# WiLo_V1_0.net
KiCad netlist of a schematic drawn in EAGLE
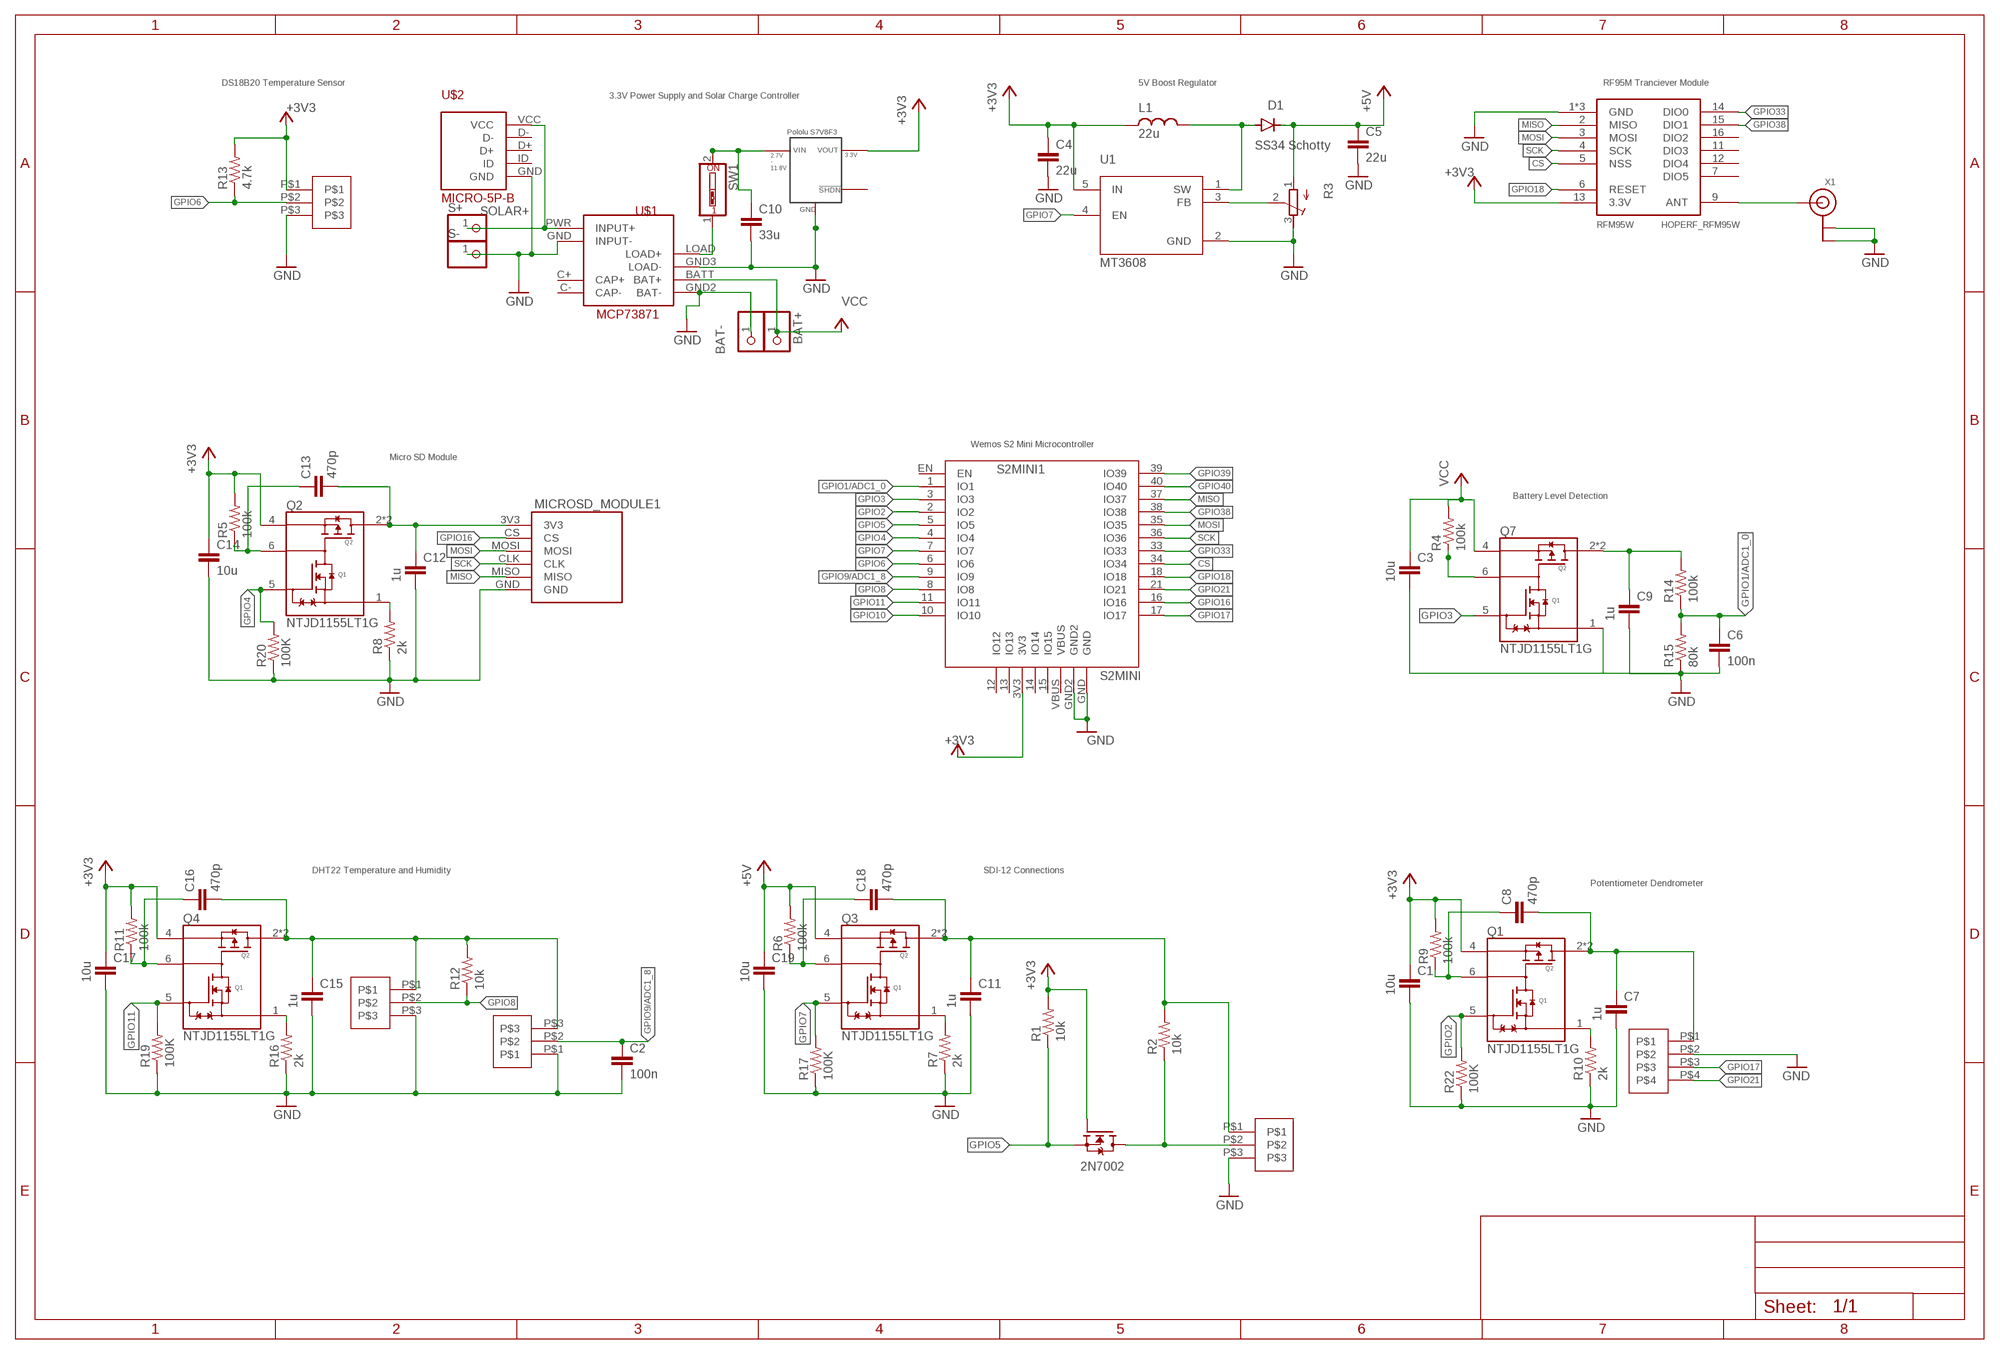
[diagram p0: schematic, sheet 1]

(export (version "E")
  (design (tool "Eeschema 10.0.6"))
  (components
    (comp (ref "BAT+")
      (value "PINHD-1X1")
      (footprint "eagle-import:1X01")
      (libsource (lib "eagle-import") (part "PINHD-1X1"))
    )
    (comp (ref "BAT-")
      (value "PINHD-1X1")
      (footprint "eagle-import:1X01")
      (libsource (lib "eagle-import") (part "PINHD-1X1"))
    )
    (comp (ref "C1")
      (value "10u")
      (footprint "eagle-import:C0805")
      (libsource (lib "eagle-import") (part "C-EUC0805"))
    )
    (comp (ref "C2")
      (value "100n")
      (footprint "eagle-import:C0805")
      (libsource (lib "eagle-import") (part "C-EUC0805"))
    )
    (comp (ref "C3")
      (value "10u")
      (footprint "eagle-import:C0805")
      (libsource (lib "eagle-import") (part "C-EUC0805"))
    )
    (comp (ref "C4")
      (value "22u")
      (footprint "eagle-import:C0805")
      (libsource (lib "eagle-import") (part "C-EUC0805"))
    )
    (comp (ref "C5")
      (value "22u")
      (footprint "eagle-import:C0805")
      (libsource (lib "eagle-import") (part "C-EUC0805"))
    )
    (comp (ref "C6")
      (value "100n")
      (footprint "eagle-import:C0805")
      (libsource (lib "eagle-import") (part "C-EUC0805"))
    )
    (comp (ref "C7")
      (value "1u")
      (footprint "eagle-import:C0805")
      (libsource (lib "eagle-import") (part "C-EUC0805"))
    )
    (comp (ref "C8")
      (value "470p")
      (footprint "eagle-import:C0805")
      (libsource (lib "eagle-import") (part "C-EUC0805"))
    )
    (comp (ref "C9")
      (value "1u")
      (footprint "eagle-import:C0805")
      (libsource (lib "eagle-import") (part "C-EUC0805"))
    )
    (comp (ref "C10")
      (value "33u")
      (footprint "eagle-import:C025-024X044")
      (libsource (lib "eagle-import") (part "C-EU025-024X044"))
    )
    (comp (ref "C11")
      (value "1u")
      (footprint "eagle-import:C0805")
      (libsource (lib "eagle-import") (part "C-EUC0805"))
    )
    (comp (ref "C12")
      (value "1u")
      (footprint "eagle-import:C0805")
      (libsource (lib "eagle-import") (part "C-EUC0805"))
    )
    (comp (ref "C13")
      (value "470p")
      (footprint "eagle-import:C0805")
      (libsource (lib "eagle-import") (part "C-EUC0805"))
    )
    (comp (ref "C14")
      (value "10u")
      (footprint "eagle-import:C0805")
      (libsource (lib "eagle-import") (part "C-EUC0805"))
    )
    (comp (ref "C15")
      (value "1u")
      (footprint "eagle-import:C0805")
      (libsource (lib "eagle-import") (part "C-EUC0805"))
    )
    (comp (ref "C16")
      (value "470p")
      (footprint "eagle-import:C0805")
      (libsource (lib "eagle-import") (part "C-EUC0805"))
    )
    (comp (ref "C17")
      (value "10u")
      (footprint "eagle-import:C0805")
      (libsource (lib "eagle-import") (part "C-EUC0805"))
    )
    (comp (ref "C18")
      (value "470p")
      (footprint "eagle-import:C0805")
      (libsource (lib "eagle-import") (part "C-EUC0805"))
    )
    (comp (ref "C19")
      (value "10u")
      (footprint "eagle-import:C0805")
      (libsource (lib "eagle-import") (part "C-EUC0805"))
    )
    (comp (ref "D1")
      (value "SS34 Schotty")
      (footprint "eagle-import:DO214BA")
      (libsource (lib "eagle-import") (part "DIODE-DO214BA"))
    )
    (comp (ref "L1")
      (value "22u")
      (footprint "eagle-import:SLF7045")
      (libsource (lib "eagle-import") (part "LSLF7045"))
    )
    (comp (ref "MICROSD_MODULE1")
      (value "GENERIC_MICROSD_MODULE")
      (footprint "eagle-import:GENERIC_MICROSD_MODULE")
      (libsource (lib "eagle-import") (part "GENERIC_MICROSD_MODULE"))
    )
    (comp (ref "Q1")
      (value "NTJD1155LT1G")
      (footprint "eagle-import:TRANS_NTJD1155LT1G")
      (fields (field (name "MF") "ON Semiconductor"))
      (libsource (lib "eagle-import") (part "NTJD1155LT1G"))
    )
    (comp (ref "Q2")
      (value "NTJD1155LT1G")
      (footprint "eagle-import:TRANS_NTJD1155LT1G")
      (fields (field (name "MF") "ON Semiconductor"))
      (libsource (lib "eagle-import") (part "NTJD1155LT1G"))
    )
    (comp (ref "Q3")
      (value "NTJD1155LT1G")
      (footprint "eagle-import:TRANS_NTJD1155LT1G")
      (fields (field (name "MF") "ON Semiconductor"))
      (libsource (lib "eagle-import") (part "NTJD1155LT1G"))
    )
    (comp (ref "Q4")
      (value "NTJD1155LT1G")
      (footprint "eagle-import:TRANS_NTJD1155LT1G")
      (fields (field (name "MF") "ON Semiconductor"))
      (libsource (lib "eagle-import") (part "NTJD1155LT1G"))
    )
    (comp (ref "Q6")
      (value "2N7002")
      (footprint "eagle-import:SOT95P240X111-3N")
      (fields (field (name "MF") "ON Semiconductor"))
      (libsource (lib "eagle-import") (part "2N7002"))
    )
    (comp (ref "Q7")
      (value "NTJD1155LT1G")
      (footprint "eagle-import:TRANS_NTJD1155LT1G")
      (fields (field (name "MF") "ON Semiconductor"))
      (libsource (lib "eagle-import") (part "NTJD1155LT1G"))
    )
    (comp (ref "R1")
      (value "10k")
      (footprint "eagle-import:R0603")
      (libsource (lib "eagle-import") (part "R-US_R0603"))
    )
    (comp (ref "R2")
      (value "10k")
      (footprint "eagle-import:R0603")
      (libsource (lib "eagle-import") (part "R-US_R0603"))
    )
    (comp (ref "R3")
      (value "R-TRIMM3296W")
      (footprint "eagle-import:RTRIM3296W")
      (libsource (lib "eagle-import") (part "R-TRIMM3296W"))
    )
    (comp (ref "R4")
      (value "100k")
      (footprint "eagle-import:R0603")
      (libsource (lib "eagle-import") (part "R-US_R0603"))
    )
    (comp (ref "R5")
      (value "100k")
      (footprint "eagle-import:R0603")
      (libsource (lib "eagle-import") (part "R-US_R0603"))
    )
    (comp (ref "R6")
      (value "100k")
      (footprint "eagle-import:R0603")
      (libsource (lib "eagle-import") (part "R-US_R0603"))
    )
    (comp (ref "R7")
      (value "2k")
      (footprint "eagle-import:R0603")
      (libsource (lib "eagle-import") (part "R-US_R0603"))
    )
    (comp (ref "R8")
      (value "2k")
      (footprint "eagle-import:R0603")
      (libsource (lib "eagle-import") (part "R-US_R0603"))
    )
    (comp (ref "R9")
      (value "100k")
      (footprint "eagle-import:R0603")
      (libsource (lib "eagle-import") (part "R-US_R0603"))
    )
    (comp (ref "R10")
      (value "2k")
      (footprint "eagle-import:R0603")
      (libsource (lib "eagle-import") (part "R-US_R0603"))
    )
    (comp (ref "R11")
      (value "100k")
      (footprint "eagle-import:R0603")
      (libsource (lib "eagle-import") (part "R-US_R0603"))
    )
    (comp (ref "R12")
      (value "10k")
      (footprint "eagle-import:R0603")
      (libsource (lib "eagle-import") (part "R-US_R0603"))
    )
    (comp (ref "R13")
      (value "4.7k")
      (footprint "eagle-import:R0603")
      (libsource (lib "eagle-import") (part "R-US_R0603"))
    )
    (comp (ref "R14")
      (value "100k")
      (footprint "eagle-import:R0603")
      (libsource (lib "eagle-import") (part "R-US_R0603"))
    )
    (comp (ref "R15")
      (value "80k")
      (footprint "eagle-import:R0603")
      (libsource (lib "eagle-import") (part "R-US_R0603"))
    )
    (comp (ref "R16")
      (value "2k")
      (footprint "eagle-import:R0603")
      (libsource (lib "eagle-import") (part "R-US_R0603"))
    )
    (comp (ref "R17")
      (value "100K")
      (footprint "eagle-import:R0603")
      (libsource (lib "eagle-import") (part "R-US_R0603"))
    )
    (comp (ref "R19")
      (value "100K")
      (footprint "eagle-import:R0603")
      (libsource (lib "eagle-import") (part "R-US_R0603"))
    )
    (comp (ref "R20")
      (value "100K")
      (footprint "eagle-import:R0603")
      (libsource (lib "eagle-import") (part "R-US_R0603"))
    )
    (comp (ref "R22")
      (value "100K")
      (footprint "eagle-import:R0603")
      (libsource (lib "eagle-import") (part "R-US_R0603"))
    )
    (comp (ref "RFM95W")
      (value "HOPERF_RFM95W")
      (footprint "eagle-import:HOPERF_RFM95W")
      (libsource (lib "eagle-import") (part "HOPERF_RFM95W"))
    )
    (comp (ref "S+")
      (value "PINHD-1X1")
      (footprint "eagle-import:1X01")
      (libsource (lib "eagle-import") (part "PINHD-1X1"))
    )
    (comp (ref "S-")
      (value "PINHD-1X1")
      (footprint "eagle-import:1X01")
      (libsource (lib "eagle-import") (part "PINHD-1X1"))
    )
    (comp (ref "S2MINI1")
      (value "S2MINI")
      (footprint "eagle-import:S2MINI")
      (libsource (lib "eagle-import") (part "S2MINI"))
    )
    (comp (ref "SW1")
      (value "SW_DIP-1")
      (footprint "eagle-import:EDG-01")
      (libsource (lib "eagle-import") (part "SW_DIP-1"))
    )
    (comp (ref "U$1")
      (value "MCP73871")
      (footprint "eagle-import:MCP73871")
      (libsource (lib "eagle-import") (part "MCP73871"))
    )
    (comp (ref "U$2")
      (value "MICRO-5P-B")
      (footprint "eagle-import:MICRO-5P-B")
      (libsource (lib "eagle-import") (part "MICRO-5P-B"))
    )
    (comp (ref "U$3")
      (value "S7V8F3")
      (footprint "eagle-import:S7V8F3")
      (libsource (lib "eagle-import") (part "S7V8F3"))
    )
    (comp (ref "U$4")
      (value "3PIN_2.54_SCREW")
      (footprint "eagle-import:3PIN_2.54_SCREW")
      (libsource (lib "eagle-import") (part "3PIN_2.54_SCREW"))
    )
    (comp (ref "U$5")
      (value "3PIN_2.54_SCREW")
      (footprint "eagle-import:3PIN_2.54_SCREW")
      (libsource (lib "eagle-import") (part "3PIN_2.54_SCREW"))
    )
    (comp (ref "U$6")
      (value "3PIN_2.54_SCREW")
      (footprint "eagle-import:3PIN_2.54_SCREW")
      (libsource (lib "eagle-import") (part "3PIN_2.54_SCREW"))
    )
    (comp (ref "U$7")
      (value "3PIN_2.54_SCREW")
      (footprint "eagle-import:3PIN_2.54_SCREW")
      (libsource (lib "eagle-import") (part "3PIN_2.54_SCREW"))
    )
    (comp (ref "U$8")
      (value "4PIN_2.54_SCREW")
      (footprint "eagle-import:4PIN_2.54_SCREW")
      (libsource (lib "eagle-import") (part "4PIN_2.54_SCREW"))
    )
    (comp (ref "U1")
      (value "MT3608")
      (footprint "eagle-import:SOT95P280X145-6N")
      (fields (field (name "MF") "Aerosemi Technology Co., Ltd"))
      (libsource (lib "eagle-import") (part "MT3608"))
    )
    (comp (ref "X1")
      (value "ANTENNA_U.FL")
      (footprint "eagle-import:U.FL")
      (libsource (lib "eagle-import") (part "ANTENNA_U.FL"))
    )
  )
  (nets
    (net (code "1") (name "+3V3") (class "Default")
      (node (ref "C1") (pin "1") (pinfunction "1_1") (pintype "passive"))
      (node (ref "C14") (pin "1") (pinfunction "1_1") (pintype "passive"))
      (node (ref "C17") (pin "1") (pinfunction "1_1") (pintype "passive"))
      (node (ref "C4") (pin "1") (pinfunction "1_1") (pintype "passive"))
      (node (ref "L1") (pin "+") (pinfunction "1_+") (pintype "passive"))
      (node (ref "Q1") (pin "4") (pinfunction "S2_4") (pintype "passive"))
      (node (ref "Q2") (pin "4") (pinfunction "S2_4") (pintype "passive"))
      (node (ref "Q4") (pin "4") (pinfunction "S2_4") (pintype "passive"))
      (node (ref "Q6") (pin "1") (pinfunction "G_1") (pintype "passive"))
      (node (ref "R1") (pin "2") (pinfunction "2_2") (pintype "passive"))
      (node (ref "R11") (pin "2") (pinfunction "2_2") (pintype "passive"))
      (node (ref "R13") (pin "2") (pinfunction "2_2") (pintype "passive"))
      (node (ref "R5") (pin "2") (pinfunction "2_2") (pintype "passive"))
      (node (ref "R9") (pin "2") (pinfunction "2_2") (pintype "passive"))
      (node (ref "RFM95W") (pin "13") (pinfunction "3.3V_13") (pintype "power_in"))
      (node (ref "S2MINI1") (pin "3V3") (pinfunction "3V3_3V3") (pintype "bidirectional"))
      (node (ref "U$3") (pin "VOUT") (pinfunction "VOUT_VOUT") (pintype "bidirectional"))
      (node (ref "U$4") (pin "P$1") (pinfunction "P$1_P$1") (pintype "bidirectional"))
      (node (ref "U1") (pin "5") (pinfunction "IN_5") (pintype "input"))
    )
    (net (code "2") (name "+5V") (class "Default")
      (node (ref "C19") (pin "1") (pinfunction "1_1") (pintype "passive"))
      (node (ref "C5") (pin "1") (pinfunction "1_1") (pintype "passive"))
      (node (ref "D1") (pin "C") (pinfunction "C_C") (pintype "passive"))
      (node (ref "Q3") (pin "4") (pinfunction "S2_4") (pintype "passive"))
      (node (ref "R3") (pin "1") (pinfunction "A_1") (pintype "passive"))
      (node (ref "R6") (pin "2") (pinfunction "2_2") (pintype "passive"))
    )
    (net (code "3") (name "/SOLAR+") (class "Default")
      (node (ref "S+") (pin "1") (pinfunction "1_1") (pintype "passive"))
      (node (ref "U$1") (pin "PWR") (pinfunction "INPUT+_PWR") (pintype "bidirectional"))
      (node (ref "U$2") (pin "VCC") (pinfunction "VCC_VCC") (pintype "bidirectional"))
    )
    (net (code "4") (name "CS") (class "Default")
      (node (ref "RFM95W") (pin "5") (pinfunction "NSS_5") (pintype "input"))
      (node (ref "S2MINI1") (pin "34") (pinfunction "IO34_34") (pintype "bidirectional"))
    )
    (net (code "5") (name "GND") (class "Default")
      (node (ref "BAT-") (pin "1") (pinfunction "1_1") (pintype "passive"))
      (node (ref "C1") (pin "2") (pinfunction "2_2") (pintype "passive"))
      (node (ref "C10") (pin "2") (pinfunction "2_2") (pintype "passive"))
      (node (ref "C11") (pin "2") (pinfunction "2_2") (pintype "passive"))
      (node (ref "C12") (pin "2") (pinfunction "2_2") (pintype "passive"))
      (node (ref "C14") (pin "2") (pinfunction "2_2") (pintype "passive"))
      (node (ref "C15") (pin "2") (pinfunction "2_2") (pintype "passive"))
      (node (ref "C17") (pin "2") (pinfunction "2_2") (pintype "passive"))
      (node (ref "C19") (pin "2") (pinfunction "2_2") (pintype "passive"))
      (node (ref "C2") (pin "2") (pinfunction "2_2") (pintype "passive"))
      (node (ref "C3") (pin "2") (pinfunction "2_2") (pintype "passive"))
      (node (ref "C4") (pin "2") (pinfunction "2_2") (pintype "passive"))
      (node (ref "C5") (pin "2") (pinfunction "2_2") (pintype "passive"))
      (node (ref "C6") (pin "2") (pinfunction "2_2") (pintype "passive"))
      (node (ref "C7") (pin "2") (pinfunction "2_2") (pintype "passive"))
      (node (ref "C9") (pin "2") (pinfunction "2_2") (pintype "passive"))
      (node (ref "MICROSD_MODULE1") (pin "GND") (pinfunction "GND_GND") (pintype "bidirectional"))
      (node (ref "Q7") (pin "1") (pinfunction "S1_1") (pintype "passive"))
      (node (ref "R10") (pin "1") (pinfunction "1_1") (pintype "passive"))
      (node (ref "R15") (pin "1") (pinfunction "1_1") (pintype "passive"))
      (node (ref "R16") (pin "1") (pinfunction "1_1") (pintype "passive"))
      (node (ref "R17") (pin "1") (pinfunction "1_1") (pintype "passive"))
      (node (ref "R19") (pin "1") (pinfunction "1_1") (pintype "passive"))
      (node (ref "R20") (pin "1") (pinfunction "1_1") (pintype "passive"))
      (node (ref "R22") (pin "1") (pinfunction "1_1") (pintype "passive"))
      (node (ref "R3") (pin "3") (pinfunction "E_3") (pintype "passive"))
      (node (ref "R7") (pin "1") (pinfunction "1_1") (pintype "passive"))
      (node (ref "R8") (pin "1") (pinfunction "1_1") (pintype "passive"))
      (node (ref "RFM95W") (pin "1") (pinfunction "GND_1") (pintype "power_in"))
      (node (ref "RFM95W") (pin "10") (pinfunction "GND_10") (pintype "power_in"))
      (node (ref "RFM95W") (pin "8") (pinfunction "GND_8") (pintype "power_in"))
      (node (ref "S-") (pin "1") (pinfunction "1_1") (pintype "passive"))
      (node (ref "S2MINI1") (pin "GND") (pinfunction "GND_GND") (pintype "bidirectional"))
      (node (ref "S2MINI1") (pin "GND2") (pinfunction "GND2_GND2") (pintype "bidirectional"))
      (node (ref "U$1") (pin "GND") (pinfunction "INPUT-_GND") (pintype "bidirectional"))
      (node (ref "U$1") (pin "GND2") (pinfunction "BAT-_GND2") (pintype "bidirectional"))
      (node (ref "U$1") (pin "GND3") (pinfunction "LOAD-_GND3") (pintype "bidirectional"))
      (node (ref "U$2") (pin "GND") (pinfunction "GND_GND") (pintype "bidirectional"))
      (node (ref "U$3") (pin "GND") (pinfunction "GND_GND") (pintype "bidirectional"))
      (node (ref "U$4") (pin "P$3") (pinfunction "P$3_P$3") (pintype "bidirectional"))
      (node (ref "U$5") (pin "P$3") (pinfunction "P$3_P$3") (pintype "bidirectional"))
      (node (ref "U$6") (pin "P$1") (pinfunction "P$1_P$1") (pintype "bidirectional"))
      (node (ref "U$7") (pin "P$3") (pinfunction "P$3_P$3") (pintype "bidirectional"))
      (node (ref "U$8") (pin "P$2") (pinfunction "P$2_P$2") (pintype "bidirectional"))
      (node (ref "U1") (pin "2") (pinfunction "GND_2") (pintype "power_in"))
      (node (ref "X1") (pin "1") (pinfunction "GND_1") (pintype "passive"))
      (node (ref "X1") (pin "2") (pinfunction "GND_2") (pintype "passive"))
    )
    (net (code "6") (name "GPIO1{slash}ADC1_0") (class "Default")
      (node (ref "C6") (pin "1") (pinfunction "1_1") (pintype "passive"))
      (node (ref "R14") (pin "1") (pinfunction "1_1") (pintype "passive"))
      (node (ref "R15") (pin "2") (pinfunction "2_2") (pintype "passive"))
      (node (ref "S2MINI1") (pin "1") (pinfunction "IO1_1") (pintype "bidirectional"))
    )
    (net (code "7") (name "GPIO2") (class "Default")
      (node (ref "Q1") (pin "5") (pinfunction "G1_5") (pintype "passive"))
      (node (ref "R22") (pin "2") (pinfunction "2_2") (pintype "passive"))
      (node (ref "S2MINI1") (pin "2") (pinfunction "IO2_2") (pintype "bidirectional"))
    )
    (net (code "8") (name "GPIO3") (class "Default")
      (node (ref "Q7") (pin "5") (pinfunction "G1_5") (pintype "passive"))
      (node (ref "S2MINI1") (pin "3") (pinfunction "IO3_3") (pintype "bidirectional"))
    )
    (net (code "9") (name "GPIO4") (class "Default")
      (node (ref "Q2") (pin "5") (pinfunction "G1_5") (pintype "passive"))
      (node (ref "R20") (pin "2") (pinfunction "2_2") (pintype "passive"))
      (node (ref "S2MINI1") (pin "4") (pinfunction "IO4_4") (pintype "bidirectional"))
    )
    (net (code "10") (name "GPIO5") (class "Default")
      (node (ref "Q6") (pin "2") (pinfunction "S_2") (pintype "passive"))
      (node (ref "R1") (pin "1") (pinfunction "1_1") (pintype "passive"))
      (node (ref "S2MINI1") (pin "5") (pinfunction "IO5_5") (pintype "bidirectional"))
    )
    (net (code "11") (name "GPIO6") (class "Default")
      (node (ref "R13") (pin "1") (pinfunction "1_1") (pintype "passive"))
      (node (ref "S2MINI1") (pin "6") (pinfunction "IO6_6") (pintype "bidirectional"))
      (node (ref "U$4") (pin "P$2") (pinfunction "P$2_P$2") (pintype "bidirectional"))
    )
    (net (code "12") (name "GPIO7") (class "Default")
      (node (ref "Q3") (pin "5") (pinfunction "G1_5") (pintype "passive"))
      (node (ref "R17") (pin "2") (pinfunction "2_2") (pintype "passive"))
      (node (ref "S2MINI1") (pin "7") (pinfunction "IO7_7") (pintype "bidirectional"))
      (node (ref "U1") (pin "4") (pinfunction "EN_4") (pintype "input"))
    )
    (net (code "13") (name "GPIO8") (class "Default")
      (node (ref "R12") (pin "1") (pinfunction "1_1") (pintype "passive"))
      (node (ref "S2MINI1") (pin "8") (pinfunction "IO8_8") (pintype "bidirectional"))
      (node (ref "U$5") (pin "P$2") (pinfunction "P$2_P$2") (pintype "bidirectional"))
    )
    (net (code "14") (name "GPIO9{slash}ADC1_8") (class "Default")
      (node (ref "C2") (pin "1") (pinfunction "1_1") (pintype "passive"))
      (node (ref "S2MINI1") (pin "9") (pinfunction "IO9_9") (pintype "bidirectional"))
      (node (ref "U$6") (pin "P$2") (pinfunction "P$2_P$2") (pintype "bidirectional"))
    )
    (net (code "15") (name "GPIO10") (class "Default")
      (node (ref "S2MINI1") (pin "10") (pinfunction "IO10_10") (pintype "bidirectional"))
    )
    (net (code "16") (name "GPIO11") (class "Default")
      (node (ref "Q4") (pin "5") (pinfunction "G1_5") (pintype "passive"))
      (node (ref "R19") (pin "2") (pinfunction "2_2") (pintype "passive"))
      (node (ref "S2MINI1") (pin "11") (pinfunction "IO11_11") (pintype "bidirectional"))
    )
    (net (code "17") (name "GPIO16") (class "Default")
      (node (ref "MICROSD_MODULE1") (pin "CS") (pinfunction "CS_CS") (pintype "bidirectional"))
      (node (ref "S2MINI1") (pin "16") (pinfunction "IO16_16") (pintype "bidirectional"))
    )
    (net (code "18") (name "GPIO17") (class "Default")
      (node (ref "S2MINI1") (pin "17") (pinfunction "IO17_17") (pintype "bidirectional"))
      (node (ref "U$8") (pin "P$3") (pinfunction "P$3_P$3") (pintype "bidirectional"))
    )
    (net (code "19") (name "GPIO18") (class "Default")
      (node (ref "RFM95W") (pin "6") (pinfunction "RESET_6") (pintype "bidirectional"))
      (node (ref "S2MINI1") (pin "18") (pinfunction "IO18_18") (pintype "bidirectional"))
    )
    (net (code "20") (name "GPIO21") (class "Default")
      (node (ref "S2MINI1") (pin "21") (pinfunction "IO21_21") (pintype "bidirectional"))
      (node (ref "U$8") (pin "P$4") (pinfunction "P$4_P$4") (pintype "bidirectional"))
    )
    (net (code "21") (name "GPIO33") (class "Default")
      (node (ref "RFM95W") (pin "14") (pinfunction "DIO0_14") (pintype "bidirectional"))
      (node (ref "S2MINI1") (pin "33") (pinfunction "IO33_33") (pintype "bidirectional"))
    )
    (net (code "22") (name "GPIO38") (class "Default")
      (node (ref "RFM95W") (pin "15") (pinfunction "DIO1_15") (pintype "bidirectional"))
      (node (ref "S2MINI1") (pin "38") (pinfunction "IO38_38") (pintype "bidirectional"))
    )
    (net (code "23") (name "GPIO39") (class "Default")
      (node (ref "S2MINI1") (pin "39") (pinfunction "IO39_39") (pintype "bidirectional"))
    )
    (net (code "24") (name "GPIO40") (class "Default")
      (node (ref "S2MINI1") (pin "40") (pinfunction "IO40_40") (pintype "bidirectional"))
    )
    (net (code "25") (name "MISO") (class "Default")
      (node (ref "MICROSD_MODULE1") (pin "MISO") (pinfunction "MISO_MISO") (pintype "bidirectional"))
      (node (ref "RFM95W") (pin "2") (pinfunction "MISO_2") (pintype "input"))
      (node (ref "S2MINI1") (pin "37") (pinfunction "IO37_37") (pintype "bidirectional"))
    )
    (net (code "26") (name "MOSI") (class "Default")
      (node (ref "MICROSD_MODULE1") (pin "MOSI") (pinfunction "MOSI_MOSI") (pintype "bidirectional"))
      (node (ref "RFM95W") (pin "3") (pinfunction "MOSI_3") (pintype "output"))
      (node (ref "S2MINI1") (pin "35") (pinfunction "IO35_35") (pintype "bidirectional"))
    )
    (net (code "27") (name "Net-(C7-Pad1)") (class "Default")
      (node (ref "C7") (pin "1") (pinfunction "1_1") (pintype "passive"))
      (node (ref "C8") (pin "2") (pinfunction "2_2") (pintype "passive"))
      (node (ref "Q1") (pin "2") (pinfunction "D2_2") (pintype "passive"))
      (node (ref "Q1") (pin "3") (pinfunction "D2_3") (pintype "passive"))
      (node (ref "U$8") (pin "P$1") (pinfunction "P$1_P$1") (pintype "bidirectional"))
    )
    (net (code "28") (name "Net-(C9-Pad1)") (class "Default")
      (node (ref "C9") (pin "1") (pinfunction "1_1") (pintype "passive"))
      (node (ref "Q7") (pin "2") (pinfunction "D2_2") (pintype "passive"))
      (node (ref "Q7") (pin "3") (pinfunction "D2_3") (pintype "passive"))
      (node (ref "R14") (pin "2") (pinfunction "2_2") (pintype "passive"))
    )
    (net (code "29") (name "Net-(C10-Pad1)") (class "Default")
      (node (ref "C10") (pin "1") (pinfunction "1_1") (pintype "passive"))
      (node (ref "SW1") (pin "2") (pinfunction "2_2") (pintype "passive"))
      (node (ref "U$3") (pin "VIN") (pinfunction "VIN_VIN") (pintype "bidirectional"))
    )
    (net (code "30") (name "Net-(C11-Pad1)") (class "Default")
      (node (ref "C11") (pin "1") (pinfunction "1_1") (pintype "passive"))
      (node (ref "C18") (pin "2") (pinfunction "2_2") (pintype "passive"))
      (node (ref "Q3") (pin "2") (pinfunction "D2_2") (pintype "passive"))
      (node (ref "Q3") (pin "3") (pinfunction "D2_3") (pintype "passive"))
      (node (ref "R2") (pin "2") (pinfunction "2_2") (pintype "passive"))
      (node (ref "U$7") (pin "P$1") (pinfunction "P$1_P$1") (pintype "bidirectional"))
    )
    (net (code "31") (name "Net-(C12-Pad1)") (class "Default")
      (node (ref "C12") (pin "1") (pinfunction "1_1") (pintype "passive"))
      (node (ref "C13") (pin "2") (pinfunction "2_2") (pintype "passive"))
      (node (ref "MICROSD_MODULE1") (pin "3V3") (pinfunction "3V3_3V3") (pintype "bidirectional"))
      (node (ref "Q2") (pin "2") (pinfunction "D2_2") (pintype "passive"))
      (node (ref "Q2") (pin "3") (pinfunction "D2_3") (pintype "passive"))
    )
    (net (code "32") (name "Net-(C15-Pad1)") (class "Default")
      (node (ref "C15") (pin "1") (pinfunction "1_1") (pintype "passive"))
      (node (ref "C16") (pin "2") (pinfunction "2_2") (pintype "passive"))
      (node (ref "Q4") (pin "2") (pinfunction "D2_2") (pintype "passive"))
      (node (ref "Q4") (pin "3") (pinfunction "D2_3") (pintype "passive"))
      (node (ref "R12") (pin "2") (pinfunction "2_2") (pintype "passive"))
      (node (ref "U$5") (pin "P$1") (pinfunction "P$1_P$1") (pintype "bidirectional"))
      (node (ref "U$6") (pin "P$3") (pinfunction "P$3_P$3") (pintype "bidirectional"))
    )
    (net (code "33") (name "Net-(L1-2)") (class "Default")
      (node (ref "D1") (pin "A") (pinfunction "A_A") (pintype "passive"))
      (node (ref "L1") (pin "-") (pinfunction "2_-") (pintype "passive"))
      (node (ref "U1") (pin "1") (pinfunction "SW_1") (pintype "output"))
    )
    (net (code "34") (name "Net-(Q1-D1{slash}G2)") (class "Default")
      (node (ref "C8") (pin "1") (pinfunction "1_1") (pintype "passive"))
      (node (ref "Q1") (pin "6") (pinfunction "D1/G2_6") (pintype "passive"))
      (node (ref "R9") (pin "1") (pinfunction "1_1") (pintype "passive"))
    )
    (net (code "35") (name "Net-(Q1-S1)") (class "Default")
      (node (ref "Q1") (pin "1") (pinfunction "S1_1") (pintype "passive"))
      (node (ref "R10") (pin "2") (pinfunction "2_2") (pintype "passive"))
    )
    (net (code "36") (name "Net-(Q2-D1{slash}G2)") (class "Default")
      (node (ref "C13") (pin "1") (pinfunction "1_1") (pintype "passive"))
      (node (ref "Q2") (pin "6") (pinfunction "D1/G2_6") (pintype "passive"))
      (node (ref "R5") (pin "1") (pinfunction "1_1") (pintype "passive"))
    )
    (net (code "37") (name "Net-(Q2-S1)") (class "Default")
      (node (ref "Q2") (pin "1") (pinfunction "S1_1") (pintype "passive"))
      (node (ref "R8") (pin "2") (pinfunction "2_2") (pintype "passive"))
    )
    (net (code "38") (name "Net-(Q3-D1{slash}G2)") (class "Default")
      (node (ref "C18") (pin "1") (pinfunction "1_1") (pintype "passive"))
      (node (ref "Q3") (pin "6") (pinfunction "D1/G2_6") (pintype "passive"))
      (node (ref "R6") (pin "1") (pinfunction "1_1") (pintype "passive"))
    )
    (net (code "39") (name "Net-(Q3-S1)") (class "Default")
      (node (ref "Q3") (pin "1") (pinfunction "S1_1") (pintype "passive"))
      (node (ref "R7") (pin "2") (pinfunction "2_2") (pintype "passive"))
    )
    (net (code "40") (name "Net-(Q4-D1{slash}G2)") (class "Default")
      (node (ref "C16") (pin "1") (pinfunction "1_1") (pintype "passive"))
      (node (ref "Q4") (pin "6") (pinfunction "D1/G2_6") (pintype "passive"))
      (node (ref "R11") (pin "1") (pinfunction "1_1") (pintype "passive"))
    )
    (net (code "41") (name "Net-(Q4-S1)") (class "Default")
      (node (ref "Q4") (pin "1") (pinfunction "S1_1") (pintype "passive"))
      (node (ref "R16") (pin "2") (pinfunction "2_2") (pintype "passive"))
    )
    (net (code "42") (name "Net-(Q6-D)") (class "Default")
      (node (ref "Q6") (pin "3") (pinfunction "D_3") (pintype "passive"))
      (node (ref "R2") (pin "1") (pinfunction "1_1") (pintype "passive"))
      (node (ref "U$7") (pin "P$2") (pinfunction "P$2_P$2") (pintype "bidirectional"))
    )
    (net (code "43") (name "Net-(Q7-D1{slash}G2)") (class "Default")
      (node (ref "Q7") (pin "6") (pinfunction "D1/G2_6") (pintype "passive"))
      (node (ref "R4") (pin "1") (pinfunction "1_1") (pintype "passive"))
    )
    (net (code "44") (name "Net-(R3-S)") (class "Default")
      (node (ref "R3") (pin "2") (pinfunction "S_2") (pintype "passive"))
      (node (ref "U1") (pin "3") (pinfunction "FB_3") (pintype "input"))
    )
    (net (code "45") (name "Net-(RFM95W-ANT)") (class "Default")
      (node (ref "RFM95W") (pin "9") (pinfunction "ANT_9") (pintype "bidirectional"))
      (node (ref "X1") (pin "3") (pinfunction "SIGNAL_3") (pintype "passive"))
    )
    (net (code "46") (name "Net-(U$1-LOAD+)") (class "Default")
      (node (ref "SW1") (pin "1") (pinfunction "1_1") (pintype "passive"))
      (node (ref "U$1") (pin "LOAD") (pinfunction "LOAD+_LOAD") (pintype "bidirectional"))
    )
    (net (code "47") (name "SCK") (class "Default")
      (node (ref "MICROSD_MODULE1") (pin "CLK") (pinfunction "CLK_CLK") (pintype "bidirectional"))
      (node (ref "RFM95W") (pin "4") (pinfunction "SCK_4") (pintype "input"))
      (node (ref "S2MINI1") (pin "36") (pinfunction "IO36_36") (pintype "bidirectional"))
    )
    (net (code "48") (name "VCC") (class "Default")
      (node (ref "BAT+") (pin "1") (pinfunction "1_1") (pintype "passive"))
      (node (ref "C3") (pin "1") (pinfunction "1_1") (pintype "passive"))
      (node (ref "Q7") (pin "4") (pinfunction "S2_4") (pintype "passive"))
      (node (ref "R4") (pin "2") (pinfunction "2_2") (pintype "passive"))
      (node (ref "U$1") (pin "BATT") (pinfunction "BAT+_BATT") (pintype "bidirectional"))
    )
    (net (code "49") (name "unconnected-(RFM95W-DIO2-Pad16)") (class "Default")
      (node (ref "RFM95W") (pin "16") (pinfunction "DIO2_16") (pintype "bidirectional"))
    )
    (net (code "50") (name "unconnected-(RFM95W-DIO3-Pad11)") (class "Default")
      (node (ref "RFM95W") (pin "11") (pinfunction "DIO3_11") (pintype "bidirectional"))
    )
    (net (code "51") (name "unconnected-(RFM95W-DIO4-Pad12)") (class "Default")
      (node (ref "RFM95W") (pin "12") (pinfunction "DIO4_12") (pintype "bidirectional"))
    )
    (net (code "52") (name "unconnected-(RFM95W-DIO5-Pad7)") (class "Default")
      (node (ref "RFM95W") (pin "7") (pinfunction "DIO5_7") (pintype "bidirectional"))
    )
    (net (code "53") (name "unconnected-(S2MINI1-IO12-Pad12)") (class "Default")
      (node (ref "S2MINI1") (pin "12") (pinfunction "IO12_12") (pintype "bidirectional"))
    )
    (net (code "54") (name "unconnected-(S2MINI1-IO13-Pad13)") (class "Default")
      (node (ref "S2MINI1") (pin "13") (pinfunction "IO13_13") (pintype "bidirectional"))
    )
    (net (code "55") (name "unconnected-(S2MINI1-IO14-Pad14)") (class "Default")
      (node (ref "S2MINI1") (pin "14") (pinfunction "IO14_14") (pintype "bidirectional"))
    )
    (net (code "56") (name "unconnected-(S2MINI1-IO15-Pad15)") (class "Default")
      (node (ref "S2MINI1") (pin "15") (pinfunction "IO15_15") (pintype "bidirectional"))
    )
    (net (code "57") (name "unconnected-(S2MINI1-PadEN)") (class "Default")
      (node (ref "S2MINI1") (pin "EN") (pinfunction "EN_EN") (pintype "bidirectional"))
    )
    (net (code "58") (name "unconnected-(S2MINI1-PadVBUS)") (class "Default")
      (node (ref "S2MINI1") (pin "VBUS") (pinfunction "VBUS_VBUS") (pintype "bidirectional"))
    )
    (net (code "59") (name "unconnected-(U$1-CAP+-PadC+)") (class "Default")
      (node (ref "U$1") (pin "C+") (pinfunction "CAP+_C+") (pintype "bidirectional"))
    )
    (net (code "60") (name "unconnected-(U$1-CAP--PadC-)") (class "Default")
      (node (ref "U$1") (pin "C-") (pinfunction "CAP-_C-") (pintype "bidirectional"))
    )
    (net (code "61") (name "unconnected-(U$2-PadD+)") (class "Default")
      (node (ref "U$2") (pin "D+") (pinfunction "D+_D+") (pintype "bidirectional"))
    )
    (net (code "62") (name "unconnected-(U$2-PadD-)") (class "Default")
      (node (ref "U$2") (pin "D-") (pinfunction "D-_D-") (pintype "bidirectional"))
    )
    (net (code "63") (name "unconnected-(U$2-PadID)") (class "Default")
      (node (ref "U$2") (pin "ID") (pinfunction "ID_ID") (pintype "bidirectional"))
    )
    (net (code "64") (name "unconnected-(U$3-~{SHDN}-Pad!SHDN)") (class "Default")
      (node (ref "U$3") (pin "!SHDN") (pinfunction "~{SHDN}_!SHDN") (pintype "bidirectional"))
    )
  )
)
